# host-mcu.net
KiCad netlist of a schematic drawn in Altium Designer
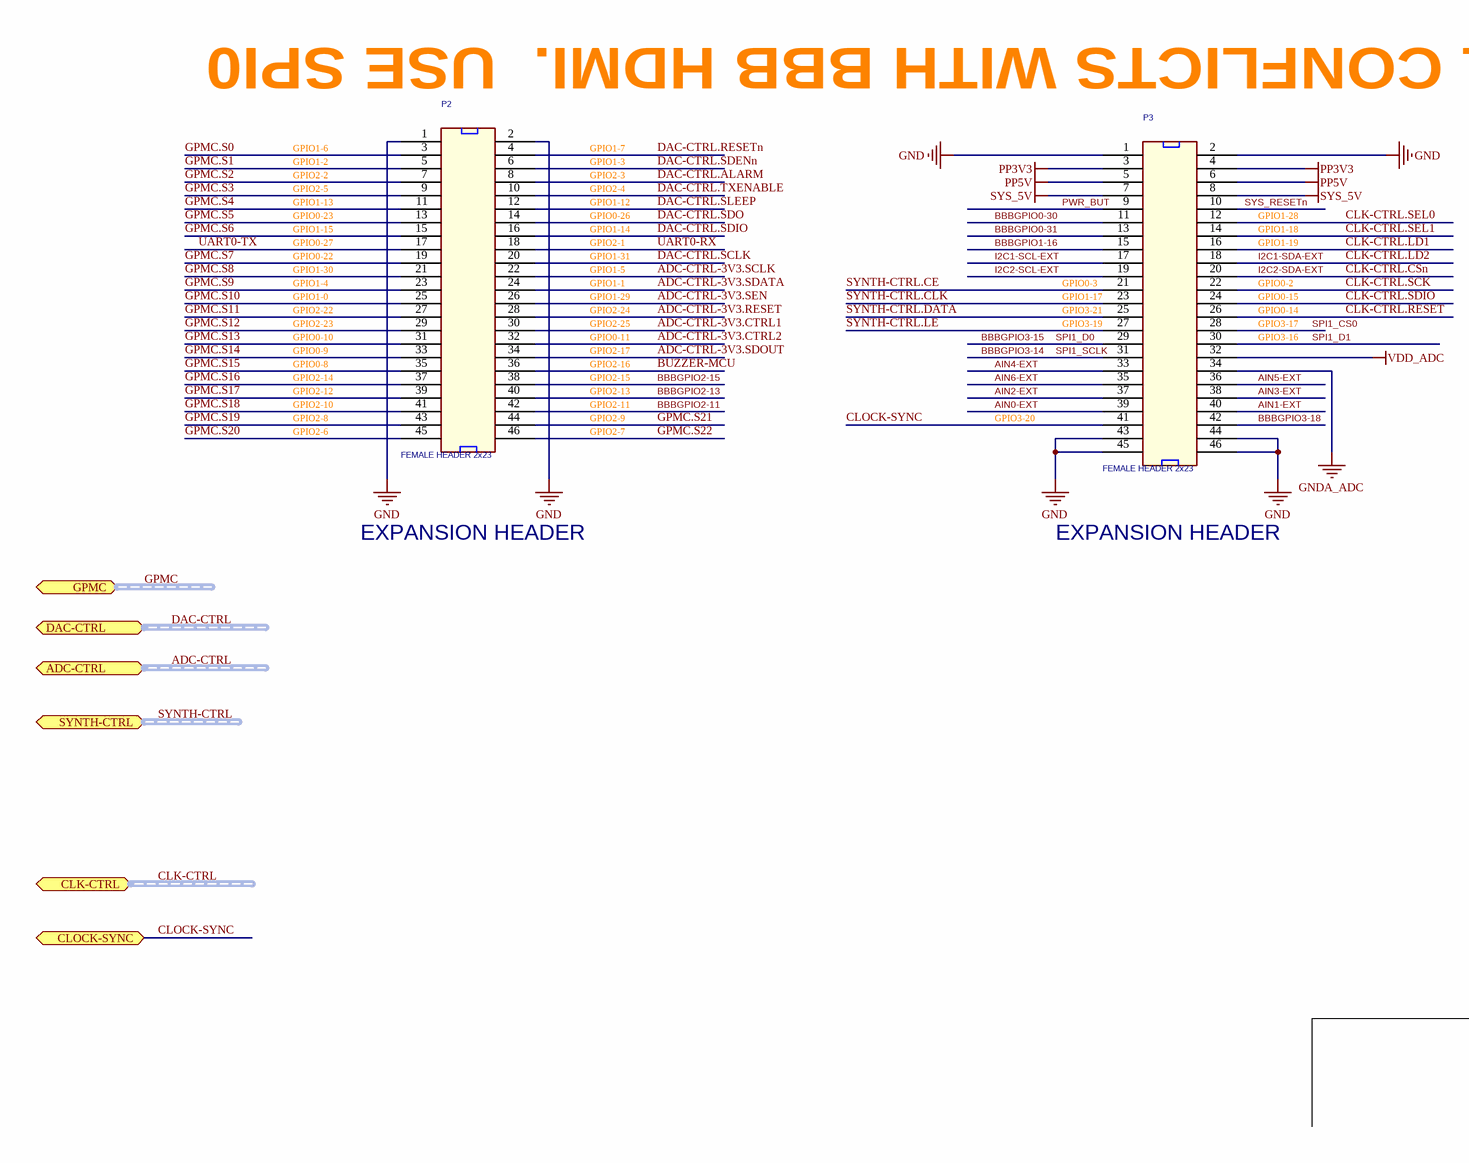
[diagram p0: host-mcu.SchDoc, left]
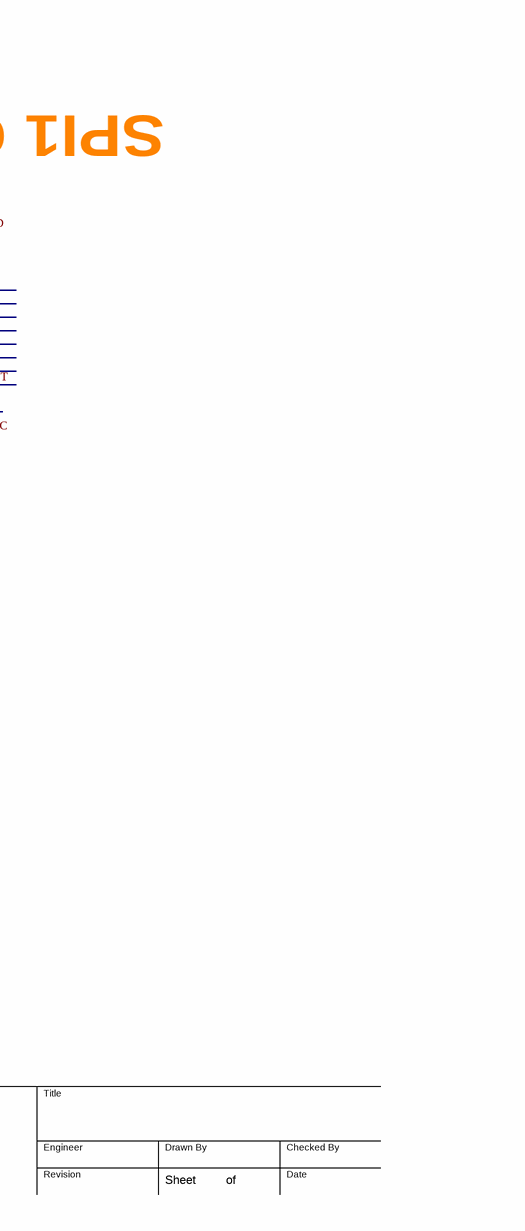
[diagram p1: host-mcu.SchDoc, right]

(export (version "E")
  (design (tool "Eeschema 10.0.6"))
  (components
    (comp (ref "P2")
      (value "FEMALE HEADER 2x23")
      (description "CONN HEADER FMAL 46PS.1\" DL GOLD")
      (fields (field (name "MANUFACTURER") "Adafruit"))
      (libsource (lib "BEAGLEBONEBLACK_REV A5B") (part "HDR_46_F_2_0.1_0.1"))
    )
    (comp (ref "P3")
      (value "FEMALE HEADER 2x23")
      (description "CONN HEADER FMAL 46PS.1\" DL GOLD")
      (fields (field (name "MANUFACTURER") "Adafruit"))
      (libsource (lib "BEAGLEBONEBLACK_REV A5B") (part "HDR_46_F_2_0.1_0.1"))
    )
  )
  (nets
    (net (code "6") (name "/ADC-CTRL-3V3.CTRL1") (class "Default")
      (node (ref "P2") (pin "30") (pinfunction "40_30") (pintype "passive"))
    )
    (net (code "7") (name "/ADC-CTRL-3V3.CTRL2") (class "Default")
      (node (ref "P2") (pin "32") (pinfunction "41_32") (pintype "passive"))
    )
    (net (code "8") (name "/ADC-CTRL-3V3.RESET") (class "Default")
      (node (ref "P2") (pin "28") (pinfunction "39_28") (pintype "passive"))
    )
    (net (code "9") (name "/ADC-CTRL-3V3.SCLK") (class "Default")
      (node (ref "P2") (pin "22") (pinfunction "36_22") (pintype "passive"))
    )
    (net (code "10") (name "/ADC-CTRL-3V3.SDATA") (class "Default")
      (node (ref "P2") (pin "24") (pinfunction "37_24") (pintype "passive"))
    )
    (net (code "11") (name "/ADC-CTRL-3V3.SDOUT") (class "Default")
      (node (ref "P2") (pin "34") (pinfunction "42_34") (pintype "passive"))
    )
    (net (code "12") (name "/ADC-CTRL-3V3.SEN") (class "Default")
      (node (ref "P2") (pin "26") (pinfunction "38_26") (pintype "passive"))
    )
    (net (code "13") (name "/AIN0-EXT") (class "Default")
      (node (ref "P3") (pin "39") (pinfunction "20_39") (pintype "passive"))
    )
    (net (code "14") (name "/AIN1-EXT") (class "Default")
      (node (ref "P3") (pin "40") (pinfunction "45_40") (pintype "passive"))
    )
    (net (code "15") (name "/AIN2-EXT") (class "Default")
      (node (ref "P3") (pin "37") (pinfunction "19_37") (pintype "passive"))
    )
    (net (code "16") (name "/AIN3-EXT") (class "Default")
      (node (ref "P3") (pin "38") (pinfunction "44_38") (pintype "passive"))
    )
    (net (code "17") (name "/AIN4-EXT") (class "Default")
      (node (ref "P3") (pin "33") (pinfunction "17_33") (pintype "passive"))
    )
    (net (code "18") (name "/AIN5-EXT") (class "Default")
      (node (ref "P3") (pin "36") (pinfunction "43_36") (pintype "passive"))
    )
    (net (code "19") (name "/AIN6-EXT") (class "Default")
      (node (ref "P3") (pin "35") (pinfunction "18_35") (pintype "passive"))
    )
    (net (code "20") (name "/BBBGPIO0-30") (class "Default")
      (node (ref "P3") (pin "11") (pinfunction "6_11") (pintype "passive"))
    )
    (net (code "21") (name "/BBBGPIO0-31") (class "Default")
      (node (ref "P3") (pin "13") (pinfunction "7_13") (pintype "passive"))
    )
    (net (code "22") (name "/BBBGPIO1-16") (class "Default")
      (node (ref "P3") (pin "15") (pinfunction "8_15") (pintype "passive"))
    )
    (net (code "23") (name "/BBBGPIO2-11") (class "Default")
      (node (ref "P2") (pin "42") (pinfunction "46_42") (pintype "passive"))
    )
    (net (code "24") (name "/BBBGPIO2-13") (class "Default")
      (node (ref "P2") (pin "40") (pinfunction "45_40") (pintype "passive"))
    )
    (net (code "25") (name "/BBBGPIO2-15") (class "Default")
      (node (ref "P2") (pin "38") (pinfunction "44_38") (pintype "passive"))
    )
    (net (code "26") (name "/BBBGPIO3-14") (class "Default")
      (node (ref "P3") (pin "31") (pinfunction "16_31") (pintype "passive"))
    )
    (net (code "27") (name "/BBBGPIO3-15") (class "Default")
      (node (ref "P3") (pin "29") (pinfunction "15_29") (pintype "passive"))
    )
    (net (code "28") (name "/BBBGPIO3-18") (class "Default")
      (node (ref "P3") (pin "42") (pinfunction "46_42") (pintype "passive"))
    )
    (net (code "29") (name "/BUZZER-MCU") (class "Default")
      (node (ref "P2") (pin "36") (pinfunction "43_36") (pintype "passive"))
    )
    (net (code "30") (name "/CLK-CTRL.CSn") (class "Default")
      (node (ref "P3") (pin "20") (pinfunction "35_20") (pintype "passive"))
    )
    (net (code "31") (name "/CLK-CTRL.LD1") (class "Default")
      (node (ref "P3") (pin "16") (pinfunction "33_16") (pintype "passive"))
    )
    (net (code "32") (name "/CLK-CTRL.LD2") (class "Default")
      (node (ref "P3") (pin "18") (pinfunction "34_18") (pintype "passive"))
    )
    (net (code "33") (name "/CLK-CTRL.RESET") (class "Default")
      (node (ref "P3") (pin "26") (pinfunction "38_26") (pintype "passive"))
    )
    (net (code "34") (name "/CLK-CTRL.SCK") (class "Default")
      (node (ref "P3") (pin "22") (pinfunction "36_22") (pintype "passive"))
    )
    (net (code "35") (name "/CLK-CTRL.SDIO") (class "Default")
      (node (ref "P3") (pin "24") (pinfunction "37_24") (pintype "passive"))
    )
    (net (code "36") (name "/CLK-CTRL.SEL0") (class "Default")
      (node (ref "P3") (pin "12") (pinfunction "31_12") (pintype "passive"))
    )
    (net (code "37") (name "/CLK-CTRL.SEL1") (class "Default")
      (node (ref "P3") (pin "14") (pinfunction "32_14") (pintype "passive"))
    )
    (net (code "38") (name "/CLOCK-SYNC") (class "Default")
      (node (ref "P3") (pin "41") (pinfunction "21_41") (pintype "passive"))
    )
    (net (code "39") (name "/DAC-CTRL.ALARM") (class "Default")
      (node (ref "P2") (pin "8") (pinfunction "29_8") (pintype "passive"))
    )
    (net (code "40") (name "/DAC-CTRL.RESETn") (class "Default")
      (node (ref "P2") (pin "4") (pinfunction "27_4") (pintype "passive"))
    )
    (net (code "41") (name "/DAC-CTRL.SCLK") (class "Default")
      (node (ref "P2") (pin "20") (pinfunction "35_20") (pintype "passive"))
    )
    (net (code "42") (name "/DAC-CTRL.SDENn") (class "Default")
      (node (ref "P2") (pin "6") (pinfunction "28_6") (pintype "passive"))
    )
    (net (code "43") (name "/DAC-CTRL.SDIO") (class "Default")
      (node (ref "P2") (pin "16") (pinfunction "33_16") (pintype "passive"))
    )
    (net (code "44") (name "/DAC-CTRL.SDO") (class "Default")
      (node (ref "P2") (pin "14") (pinfunction "32_14") (pintype "passive"))
    )
    (net (code "45") (name "/DAC-CTRL.SLEEP") (class "Default")
      (node (ref "P2") (pin "12") (pinfunction "31_12") (pintype "passive"))
    )
    (net (code "46") (name "/DAC-CTRL.TXENABLE") (class "Default")
      (node (ref "P2") (pin "10") (pinfunction "30_10") (pintype "passive"))
    )
    (net (code "47") (name "/GPMC.S0") (class "Default")
      (node (ref "P2") (pin "3") (pinfunction "2_3") (pintype "passive"))
    )
    (net (code "48") (name "/GPMC.S1") (class "Default")
      (node (ref "P2") (pin "5") (pinfunction "3_5") (pintype "passive"))
    )
    (net (code "49") (name "/GPMC.S2") (class "Default")
      (node (ref "P2") (pin "7") (pinfunction "4_7") (pintype "passive"))
    )
    (net (code "50") (name "/GPMC.S3") (class "Default")
      (node (ref "P2") (pin "9") (pinfunction "5_9") (pintype "passive"))
    )
    (net (code "51") (name "/GPMC.S4") (class "Default")
      (node (ref "P2") (pin "11") (pinfunction "6_11") (pintype "passive"))
    )
    (net (code "52") (name "/GPMC.S5") (class "Default")
      (node (ref "P2") (pin "13") (pinfunction "7_13") (pintype "passive"))
    )
    (net (code "53") (name "/GPMC.S6") (class "Default")
      (node (ref "P2") (pin "15") (pinfunction "8_15") (pintype "passive"))
    )
    (net (code "54") (name "/GPMC.S7") (class "Default")
      (node (ref "P2") (pin "19") (pinfunction "10_19") (pintype "passive"))
    )
    (net (code "55") (name "/GPMC.S8") (class "Default")
      (node (ref "P2") (pin "21") (pinfunction "11_21") (pintype "passive"))
    )
    (net (code "56") (name "/GPMC.S9") (class "Default")
      (node (ref "P2") (pin "23") (pinfunction "12_23") (pintype "passive"))
    )
    (net (code "57") (name "/GPMC.S10") (class "Default")
      (node (ref "P2") (pin "25") (pinfunction "13_25") (pintype "passive"))
    )
    (net (code "58") (name "/GPMC.S11") (class "Default")
      (node (ref "P2") (pin "27") (pinfunction "14_27") (pintype "passive"))
    )
    (net (code "59") (name "/GPMC.S12") (class "Default")
      (node (ref "P2") (pin "29") (pinfunction "15_29") (pintype "passive"))
    )
    (net (code "60") (name "/GPMC.S13") (class "Default")
      (node (ref "P2") (pin "31") (pinfunction "16_31") (pintype "passive"))
    )
    (net (code "61") (name "/GPMC.S14") (class "Default")
      (node (ref "P2") (pin "33") (pinfunction "17_33") (pintype "passive"))
    )
    (net (code "62") (name "/GPMC.S15") (class "Default")
      (node (ref "P2") (pin "35") (pinfunction "18_35") (pintype "passive"))
    )
    (net (code "63") (name "/GPMC.S16") (class "Default")
      (node (ref "P2") (pin "37") (pinfunction "19_37") (pintype "passive"))
    )
    (net (code "64") (name "/GPMC.S17") (class "Default")
      (node (ref "P2") (pin "39") (pinfunction "20_39") (pintype "passive"))
    )
    (net (code "65") (name "/GPMC.S18") (class "Default")
      (node (ref "P2") (pin "41") (pinfunction "21_41") (pintype "passive"))
    )
    (net (code "66") (name "/GPMC.S19") (class "Default")
      (node (ref "P2") (pin "43") (pinfunction "22_43") (pintype "passive"))
    )
    (net (code "67") (name "/GPMC.S20") (class "Default")
      (node (ref "P2") (pin "45") (pinfunction "23_45") (pintype "passive"))
    )
    (net (code "68") (name "/GPMC.S21") (class "Default")
      (node (ref "P2") (pin "44") (pinfunction "47_44") (pintype "passive"))
    )
    (net (code "69") (name "/GPMC.S22") (class "Default")
      (node (ref "P2") (pin "46") (pinfunction "48_46") (pintype "passive"))
    )
    (net (code "70") (name "/I2C1-SCL-EXT") (class "Default")
      (node (ref "P3") (pin "17") (pinfunction "9_17") (pintype "passive"))
    )
    (net (code "71") (name "/I2C2-SCL-EXT") (class "Default")
      (node (ref "P3") (pin "19") (pinfunction "10_19") (pintype "passive"))
    )
    (net (code "72") (name "/PWR_BUT") (class "Default")
      (node (ref "P3") (pin "9") (pinfunction "5_9") (pintype "passive"))
    )
    (net (code "73") (name "/SPI1_CS0") (class "Default")
      (node (ref "P3") (pin "28") (pinfunction "39_28") (pintype "passive"))
    )
    (net (code "74") (name "/SPI1_D1") (class "Default")
      (node (ref "P3") (pin "30") (pinfunction "40_30") (pintype "passive"))
    )
    (net (code "75") (name "/SYNTH-CTRL.CE") (class "Default")
      (node (ref "P3") (pin "21") (pinfunction "11_21") (pintype "passive"))
    )
    (net (code "76") (name "/SYNTH-CTRL.CLK") (class "Default")
      (node (ref "P3") (pin "23") (pinfunction "12_23") (pintype "passive"))
    )
    (net (code "77") (name "/SYNTH-CTRL.DATA") (class "Default")
      (node (ref "P3") (pin "25") (pinfunction "13_25") (pintype "passive"))
    )
    (net (code "78") (name "/SYNTH-CTRL.LE") (class "Default")
      (node (ref "P3") (pin "27") (pinfunction "14_27") (pintype "passive"))
    )
    (net (code "79") (name "/SYS_RESETn") (class "Default")
      (node (ref "P3") (pin "10") (pinfunction "30_10") (pintype "passive"))
    )
    (net (code "80") (name "/UART0-RX") (class "Default")
      (node (ref "P2") (pin "18") (pinfunction "34_18") (pintype "passive"))
    )
    (net (code "81") (name "/UART0-TX") (class "Default")
      (node (ref "P2") (pin "17") (pinfunction "9_17") (pintype "passive"))
    )
    (net (code "87") (name "GND") (class "Default")
      (node (ref "P2") (pin "1") (pinfunction "1_1") (pintype "passive"))
      (node (ref "P2") (pin "2") (pinfunction "26_2") (pintype "passive"))
      (node (ref "P3") (pin "1") (pinfunction "1_1") (pintype "passive"))
      (node (ref "P3") (pin "2") (pinfunction "26_2") (pintype "passive"))
      (node (ref "P3") (pin "43") (pinfunction "22_43") (pintype "passive"))
      (node (ref "P3") (pin "44") (pinfunction "47_44") (pintype "passive"))
      (node (ref "P3") (pin "45") (pinfunction "23_45") (pintype "passive"))
      (node (ref "P3") (pin "46") (pinfunction "48_46") (pintype "passive"))
    )
    (net (code "88") (name "GNDA_ADC") (class "Default")
      (node (ref "P3") (pin "34") (pinfunction "42_34") (pintype "passive"))
    )
    (net (code "89") (name "PP3V3") (class "Default")
      (node (ref "P3") (pin "3") (pinfunction "2_3") (pintype "passive"))
      (node (ref "P3") (pin "4") (pinfunction "27_4") (pintype "passive"))
    )
    (net (code "90") (name "PP5V") (class "Default")
      (node (ref "P3") (pin "5") (pinfunction "3_5") (pintype "passive"))
      (node (ref "P3") (pin "6") (pinfunction "28_6") (pintype "passive"))
    )
    (net (code "91") (name "SYS_5V") (class "Default")
      (node (ref "P3") (pin "7") (pinfunction "4_7") (pintype "passive"))
      (node (ref "P3") (pin "8") (pinfunction "29_8") (pintype "passive"))
    )
    (net (code "92") (name "VDD_ADC") (class "Default")
      (node (ref "P3") (pin "32") (pinfunction "41_32") (pintype "passive"))
    )
  )
)
